# RS485Comm.net
KiCad netlist of a schematic drawn in Altium Designer
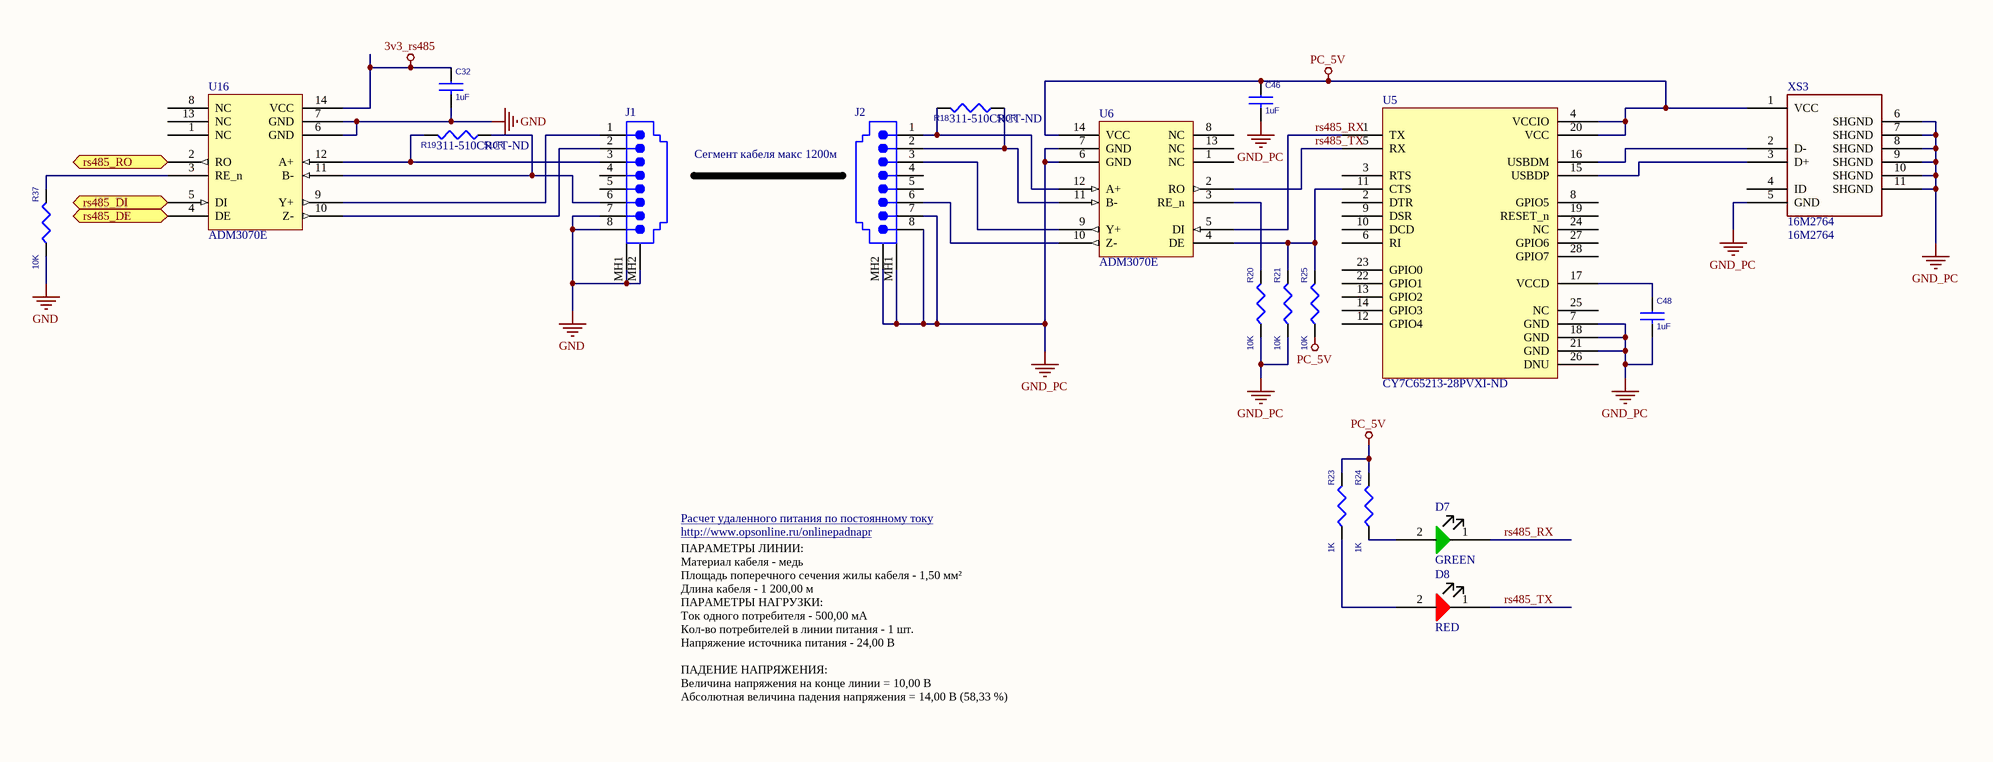
[diagram p0: RS485Comm.SchDoc]

(export (version "E")
  (design (tool "Eeschema 10.0.6"))
  (components
    (comp (ref "C32")
      (value "1uF")
      (footprint "CAPC2012X09M")
      (description "MLCC; 1uF; 25V; X7R; ±10%; SMD; 0805;")
      (libsource (lib "Capacitors") (part "CAP_SMD_1uF_10%"))
    )
    (comp (ref "C46")
      (value "1uF")
      (footprint "CAPC2012X09M")
      (description "MLCC; 1uF; 25V; X7R; ±10%; SMD; 0805;")
      (libsource (lib "Capacitors") (part "CAP_SMD_1uF_10%"))
    )
    (comp (ref "C48")
      (value "1uF")
      (footprint "CAPC2012X09M")
      (description "MLCC; 1uF; 25V; X7R; ±10%; SMD; 0805;")
      (libsource (lib "Capacitors") (part "CAP_SMD_1uF_10%"))
    )
    (comp (ref "D7")
      (value "GREEN")
      (footprint "DIOC2012X11N")
      (libsource (lib "Passive") (part "LED_GREEN"))
    )
    (comp (ref "D8") (value "RED") (footprint "DIOC2012X11N") (libsource (lib "Passive") (part "LED_RED")))
    (comp (ref "J1")
      (value "RJ-45")
      (footprint "RJ-45_PCB")
      (description "High-Speed, Vertical, Standard Profile, Internal Shield PCB Jack")
      (libsource (lib "Connectors") (part "RJ-45"))
    )
    (comp (ref "J2")
      (value "RJ-45")
      (footprint "RJ-45_PCB")
      (description "High-Speed, Vertical, Standard Profile, Internal Shield PCB Jack")
      (libsource (lib "Connectors") (part "RJ-45"))
    )
    (comp (ref "R18")
      (value "510R")
      (footprint "RESC2013X06M")
      (description "RES - 510 OHM, 5%, 1/8W, 0805 SMD")
      (fields (field (name "SUPPLIER PART NUMBER 1") "311-510CRCT-ND"))
      (libsource (lib "Resistors") (part "RES_SMD_510_5%"))
    )
    (comp (ref "R19")
      (value "510R")
      (footprint "RESC2013X06M")
      (description "RES - 510 OHM, 5%, 1/8W, 0805 SMD")
      (fields (field (name "SUPPLIER PART NUMBER 1") "311-510CRCT-ND"))
      (libsource (lib "Resistors") (part "RES_SMD_510_5%"))
    )
    (comp (ref "R20")
      (value "10K")
      (footprint "RESC2013X06M")
      (description "RES 10K OHM 1/8W 5% 0805 SMD")
      (libsource (lib "Resistors") (part "RES_SMD_10K_5%"))
    )
    (comp (ref "R21")
      (value "10K")
      (footprint "RESC2013X06M")
      (description "RES 10K OHM 1/8W 5% 0805 SMD")
      (libsource (lib "Resistors") (part "RES_SMD_10K_5%"))
    )
    (comp (ref "R23")
      (value "1K")
      (footprint "RESC2013X06M")
      (description "RES - 1K OHM, 5%, 1/8W, 0805 SMD")
      (libsource (lib "Resistors") (part "RES_SMD_1K_5%"))
    )
    (comp (ref "R24")
      (value "1K")
      (footprint "RESC2013X06M")
      (description "RES - 1K OHM, 5%, 1/8W, 0805 SMD")
      (libsource (lib "Resistors") (part "RES_SMD_1K_5%"))
    )
    (comp (ref "R25")
      (value "10K")
      (footprint "RESC2013X06M")
      (description "RES 10K OHM 1/8W 5% 0805 SMD")
      (libsource (lib "Resistors") (part "RES_SMD_10K_5%"))
    )
    (comp (ref "R37")
      (value "10K")
      (footprint "RESC2013X06M")
      (description "RES 10K OHM 1/8W 5% 0805 SMD")
      (libsource (lib "Resistors") (part "RES_SMD_10K_5%"))
    )
    (comp (ref "U5")
      (value "CY7C65213")
      (footprint "SOP65P780X200-28M")
      (fields (field (name "SUPPLIER PART NUMBER 1") "CY7C65213-28PVXI-ND"))
      (libsource (lib "TruthEar") (part "CY7C65213"))
    )
    (comp (ref "U6")
      (value "ADM3070E")
      (footprint "SOIC127P600X175-14N")
      (libsource (lib "TruthEar") (part "ADM3070E"))
    )
    (comp (ref "U16")
      (value "ADM3070E")
      (footprint "SOIC127P600X175-14N")
      (libsource (lib "") (part "ADM3070E_1"))
    )
    (comp (ref "XS3")
      (value "16M2764")
      (footprint "USB_MINI_16M2764")
      (fields (field (name "SUPPLIER PART NUMBER 1") "16M2764"))
      (libsource (lib "Connectors") (part "USB_MINI_16M2764"))
    )
  )
  (nets
    (net (code "1") (name "/rs485_DE") (class "Default")
      (node (ref "U16") (pin "4") (pinfunction "DE_4") (pintype "passive"))
    )
    (net (code "2") (name "/rs485_DI") (class "Default")
      (node (ref "U16") (pin "5") (pinfunction "DI_5") (pintype "input"))
    )
    (net (code "3") (name "/rs485_RO") (class "Default")
      (node (ref "U16") (pin "2") (pinfunction "RO_2") (pintype "output"))
    )
    (net (code "4") (name "/rs485_RX") (class "Default")
      (node (ref "D7") (pin "1") (pinfunction "C_1") (pintype "passive"))
      (node (ref "U5") (pin "1") (pinfunction "TX_1") (pintype "power_in"))
      (node (ref "U6") (pin "5") (pinfunction "DI_5") (pintype "input"))
    )
    (net (code "5") (name "/rs485_TX") (class "Default")
      (node (ref "D8") (pin "1") (pinfunction "C_1") (pintype "passive"))
      (node (ref "U5") (pin "5") (pinfunction "RX_5") (pintype "power_in"))
      (node (ref "U6") (pin "2") (pinfunction "RO_2") (pintype "output"))
    )
    (net (code "6") (name "3v3_rs485") (class "Default")
      (node (ref "C32") (pin "1") (pinfunction "1_1") (pintype "passive"))
      (node (ref "U16") (pin "14") (pinfunction "VCC_14") (pintype "passive"))
    )
    (net (code "7") (name "GND") (class "Default")
      (node (ref "C32") (pin "2") (pinfunction "2_2") (pintype "passive"))
      (node (ref "J1") (pin "7") (pinfunction "7_7") (pintype "passive"))
      (node (ref "J1") (pin "8") (pinfunction "8_8") (pintype "passive"))
      (node (ref "J1") (pin "MH1") (pinfunction "Shield_MH1") (pintype "passive"))
      (node (ref "J1") (pin "MH2") (pinfunction "Shield_MH2") (pintype "passive"))
      (node (ref "R37") (pin "1") (pinfunction "1_1") (pintype "passive"))
      (node (ref "U16") (pin "6") (pinfunction "GND_6") (pintype "passive"))
      (node (ref "U16") (pin "7") (pinfunction "GND_7") (pintype "passive"))
    )
    (net (code "8") (name "GND_PC") (class "Default")
      (node (ref "C46") (pin "2") (pinfunction "2_2") (pintype "passive"))
      (node (ref "C48") (pin "2") (pinfunction "2_2") (pintype "passive"))
      (node (ref "J2") (pin "7") (pinfunction "7_7") (pintype "passive"))
      (node (ref "J2") (pin "8") (pinfunction "8_8") (pintype "passive"))
      (node (ref "J2") (pin "MH1") (pinfunction "Shield_MH1") (pintype "passive"))
      (node (ref "J2") (pin "MH2") (pinfunction "Shield_MH2") (pintype "passive"))
      (node (ref "R20") (pin "1") (pinfunction "1_1") (pintype "passive"))
      (node (ref "R21") (pin "1") (pinfunction "1_1") (pintype "passive"))
      (node (ref "U5") (pin "18") (pinfunction "GND_18") (pintype "power_in"))
      (node (ref "U5") (pin "21") (pinfunction "GND_21") (pintype "power_in"))
      (node (ref "U5") (pin "7") (pinfunction "GND_7") (pintype "power_in"))
      (node (ref "U6") (pin "6") (pinfunction "GND_6") (pintype "passive"))
      (node (ref "U6") (pin "7") (pinfunction "GND_7") (pintype "passive"))
      (node (ref "XS3") (pin "10") (pinfunction "SHGND_10") (pintype "passive"))
      (node (ref "XS3") (pin "11") (pinfunction "SHGND_11") (pintype "passive"))
      (node (ref "XS3") (pin "5") (pinfunction "GND_5") (pintype "passive"))
      (node (ref "XS3") (pin "6") (pinfunction "SHGND_6") (pintype "passive"))
      (node (ref "XS3") (pin "7") (pinfunction "SHGND_7") (pintype "passive"))
      (node (ref "XS3") (pin "8") (pinfunction "SHGND_8") (pintype "passive"))
      (node (ref "XS3") (pin "9") (pinfunction "SHGND_9") (pintype "passive"))
    )
    (net (code "9") (name "Net-(D7-A)") (class "Default")
      (node (ref "D7") (pin "2") (pinfunction "A_2") (pintype "passive"))
      (node (ref "R24") (pin "1") (pinfunction "1_1") (pintype "passive"))
    )
    (net (code "10") (name "Net-(D8-A)") (class "Default")
      (node (ref "D8") (pin "2") (pinfunction "A_2") (pintype "passive"))
      (node (ref "R23") (pin "1") (pinfunction "1_1") (pintype "passive"))
    )
    (net (code "11") (name "Net-(U5-CTS)") (class "Default")
      (node (ref "R21") (pin "2") (pinfunction "2_2") (pintype "passive"))
      (node (ref "R25") (pin "2") (pinfunction "2_2") (pintype "passive"))
      (node (ref "U5") (pin "11") (pinfunction "CTS_11") (pintype "power_in"))
      (node (ref "U6") (pin "4") (pinfunction "DE_4") (pintype "passive"))
    )
    (net (code "12") (name "Net-(U5-USBDM)") (class "Default")
      (node (ref "U5") (pin "16") (pinfunction "USBDM_16") (pintype "power_in"))
      (node (ref "XS3") (pin "2") (pinfunction "D-_2") (pintype "passive"))
    )
    (net (code "13") (name "Net-(U5-USBDP)") (class "Default")
      (node (ref "U5") (pin "15") (pinfunction "USBDP_15") (pintype "power_in"))
      (node (ref "XS3") (pin "3") (pinfunction "D+_3") (pintype "passive"))
    )
    (net (code "14") (name "Net-(U5-VCCD)") (class "Default")
      (node (ref "C48") (pin "1") (pinfunction "1_1") (pintype "passive"))
      (node (ref "U5") (pin "17") (pinfunction "VCCD_17") (pintype "power_in"))
    )
    (net (code "15") (name "Net-(U6-A+)") (class "Default")
      (node (ref "J2") (pin "1") (pinfunction "1_1") (pintype "passive"))
      (node (ref "R18") (pin "2") (pinfunction "2_2") (pintype "passive"))
      (node (ref "U6") (pin "12") (pinfunction "A+_12") (pintype "input"))
    )
    (net (code "16") (name "Net-(U6-B-)") (class "Default")
      (node (ref "J2") (pin "2") (pinfunction "2_2") (pintype "passive"))
      (node (ref "R18") (pin "1") (pinfunction "1_1") (pintype "passive"))
      (node (ref "U6") (pin "11") (pinfunction "B-_11") (pintype "input"))
    )
    (net (code "17") (name "Net-(U6-RE_n)") (class "Default")
      (node (ref "R20") (pin "2") (pinfunction "2_2") (pintype "passive"))
      (node (ref "U6") (pin "3") (pinfunction "RE_n_3") (pintype "passive"))
    )
    (net (code "18") (name "Net-(U6-Y+)") (class "Default")
      (node (ref "J2") (pin "3") (pinfunction "3_3") (pintype "passive"))
      (node (ref "U6") (pin "9") (pinfunction "Y+_9") (pintype "output"))
    )
    (net (code "19") (name "Net-(U6-Z-)") (class "Default")
      (node (ref "J2") (pin "6") (pinfunction "6_6") (pintype "passive"))
      (node (ref "U6") (pin "10") (pinfunction "Z-_10") (pintype "output"))
    )
    (net (code "20") (name "Net-(U16-A+)") (class "Default")
      (node (ref "J1") (pin "3") (pinfunction "3_3") (pintype "passive"))
      (node (ref "R19") (pin "2") (pinfunction "2_2") (pintype "passive"))
      (node (ref "U16") (pin "12") (pinfunction "A+_12") (pintype "input"))
    )
    (net (code "21") (name "Net-(U16-B-)") (class "Default")
      (node (ref "J1") (pin "6") (pinfunction "6_6") (pintype "passive"))
      (node (ref "R19") (pin "1") (pinfunction "1_1") (pintype "passive"))
      (node (ref "U16") (pin "11") (pinfunction "B-_11") (pintype "input"))
    )
    (net (code "22") (name "Net-(U16-RE_n)") (class "Default")
      (node (ref "R37") (pin "2") (pinfunction "2_2") (pintype "passive"))
      (node (ref "U16") (pin "3") (pinfunction "RE_n_3") (pintype "passive"))
    )
    (net (code "23") (name "Net-(U16-Y+)") (class "Default")
      (node (ref "J1") (pin "1") (pinfunction "1_1") (pintype "passive"))
      (node (ref "U16") (pin "9") (pinfunction "Y+_9") (pintype "output"))
    )
    (net (code "24") (name "Net-(U16-Z-)") (class "Default")
      (node (ref "J1") (pin "2") (pinfunction "2_2") (pintype "passive"))
      (node (ref "U16") (pin "10") (pinfunction "Z-_10") (pintype "output"))
    )
    (net (code "25") (name "PC_5V") (class "Default")
      (node (ref "C46") (pin "1") (pinfunction "1_1") (pintype "passive"))
      (node (ref "R23") (pin "2") (pinfunction "2_2") (pintype "passive"))
      (node (ref "R24") (pin "2") (pinfunction "2_2") (pintype "passive"))
      (node (ref "R25") (pin "1") (pinfunction "1_1") (pintype "passive"))
      (node (ref "U5") (pin "20") (pinfunction "VCC_20") (pintype "power_in"))
      (node (ref "U5") (pin "4") (pinfunction "VCCIO_4") (pintype "power_in"))
      (node (ref "U6") (pin "14") (pinfunction "VCC_14") (pintype "passive"))
      (node (ref "XS3") (pin "1") (pinfunction "VCC_1") (pintype "passive"))
    )
    (net (code "26") (name "unconnected-(J1-Pad4)") (class "Default")
      (node (ref "J1") (pin "4") (pinfunction "4_4") (pintype "passive"))
    )
    (net (code "27") (name "unconnected-(J1-Pad5)") (class "Default")
      (node (ref "J1") (pin "5") (pinfunction "5_5") (pintype "passive"))
    )
    (net (code "28") (name "unconnected-(J2-Pad4)") (class "Default")
      (node (ref "J2") (pin "4") (pinfunction "4_4") (pintype "passive"))
    )
    (net (code "29") (name "unconnected-(J2-Pad5)") (class "Default")
      (node (ref "J2") (pin "5") (pinfunction "5_5") (pintype "passive"))
    )
    (net (code "30") (name "unconnected-(U5-DCD-Pad10)") (class "Default")
      (node (ref "U5") (pin "10") (pinfunction "DCD_10") (pintype "power_in"))
    )
    (net (code "31") (name "unconnected-(U5-DNU-Pad26)") (class "Default")
      (node (ref "U5") (pin "26") (pinfunction "DNU_26") (pintype "power_in"))
    )
    (net (code "32") (name "unconnected-(U5-DSR-Pad9)") (class "Default")
      (node (ref "U5") (pin "9") (pinfunction "DSR_9") (pintype "power_in"))
    )
    (net (code "33") (name "unconnected-(U5-DTR-Pad2)") (class "Default")
      (node (ref "U5") (pin "2") (pinfunction "DTR_2") (pintype "power_in"))
    )
    (net (code "34") (name "unconnected-(U5-GPIO0-Pad23)") (class "Default")
      (node (ref "U5") (pin "23") (pinfunction "GPIO0_23") (pintype "power_in"))
    )
    (net (code "35") (name "unconnected-(U5-GPIO1-Pad22)") (class "Default")
      (node (ref "U5") (pin "22") (pinfunction "GPIO1_22") (pintype "power_in"))
    )
    (net (code "36") (name "unconnected-(U5-GPIO2-Pad13)") (class "Default")
      (node (ref "U5") (pin "13") (pinfunction "GPIO2_13") (pintype "power_in"))
    )
    (net (code "37") (name "unconnected-(U5-GPIO3-Pad14)") (class "Default")
      (node (ref "U5") (pin "14") (pinfunction "GPIO3_14") (pintype "power_in"))
    )
    (net (code "38") (name "unconnected-(U5-GPIO4-Pad12)") (class "Default")
      (node (ref "U5") (pin "12") (pinfunction "GPIO4_12") (pintype "power_in"))
    )
    (net (code "39") (name "unconnected-(U5-GPIO5-Pad8)") (class "Default")
      (node (ref "U5") (pin "8") (pinfunction "GPIO5_8") (pintype "power_in"))
    )
    (net (code "40") (name "unconnected-(U5-GPIO6-Pad27)") (class "Default")
      (node (ref "U5") (pin "27") (pinfunction "GPIO6_27") (pintype "power_in"))
    )
    (net (code "41") (name "unconnected-(U5-GPIO7-Pad28)") (class "Default")
      (node (ref "U5") (pin "28") (pinfunction "GPIO7_28") (pintype "power_in"))
    )
    (net (code "42") (name "unconnected-(U5-NC-Pad24)") (class "Default")
      (node (ref "U5") (pin "24") (pinfunction "NC_24") (pintype "power_in"))
    )
    (net (code "43") (name "unconnected-(U5-NC-Pad25)") (class "Default")
      (node (ref "U5") (pin "25") (pinfunction "NC_25") (pintype "power_in"))
    )
    (net (code "44") (name "unconnected-(U5-RESET_n-Pad19)") (class "Default")
      (node (ref "U5") (pin "19") (pinfunction "RESET_n_19") (pintype "power_in"))
    )
    (net (code "45") (name "unconnected-(U5-RI-Pad6)") (class "Default")
      (node (ref "U5") (pin "6") (pinfunction "RI_6") (pintype "power_in"))
    )
    (net (code "46") (name "unconnected-(U5-RTS-Pad3)") (class "Default")
      (node (ref "U5") (pin "3") (pinfunction "RTS_3") (pintype "power_in"))
    )
    (net (code "47") (name "unconnected-(U6-NC-Pad1)") (class "Default")
      (node (ref "U6") (pin "1") (pinfunction "NC_1") (pintype "passive"))
    )
    (net (code "48") (name "unconnected-(U6-NC-Pad8)") (class "Default")
      (node (ref "U6") (pin "8") (pinfunction "NC_8") (pintype "passive"))
    )
    (net (code "49") (name "unconnected-(U6-NC-Pad13)") (class "Default")
      (node (ref "U6") (pin "13") (pinfunction "NC_13") (pintype "passive"))
    )
    (net (code "50") (name "unconnected-(U16-NC-Pad1)") (class "Default")
      (node (ref "U16") (pin "1") (pinfunction "NC_1") (pintype "passive"))
    )
    (net (code "51") (name "unconnected-(U16-NC-Pad8)") (class "Default")
      (node (ref "U16") (pin "8") (pinfunction "NC_8") (pintype "passive"))
    )
    (net (code "52") (name "unconnected-(U16-NC-Pad13)") (class "Default")
      (node (ref "U16") (pin "13") (pinfunction "NC_13") (pintype "passive"))
    )
    (net (code "53") (name "unconnected-(XS3-ID-Pad4)") (class "Default")
      (node (ref "XS3") (pin "4") (pinfunction "ID_4") (pintype "passive"))
    )
  )
)
